# pcb.net
KiCad netlist of a schematic drawn in EasyEDA
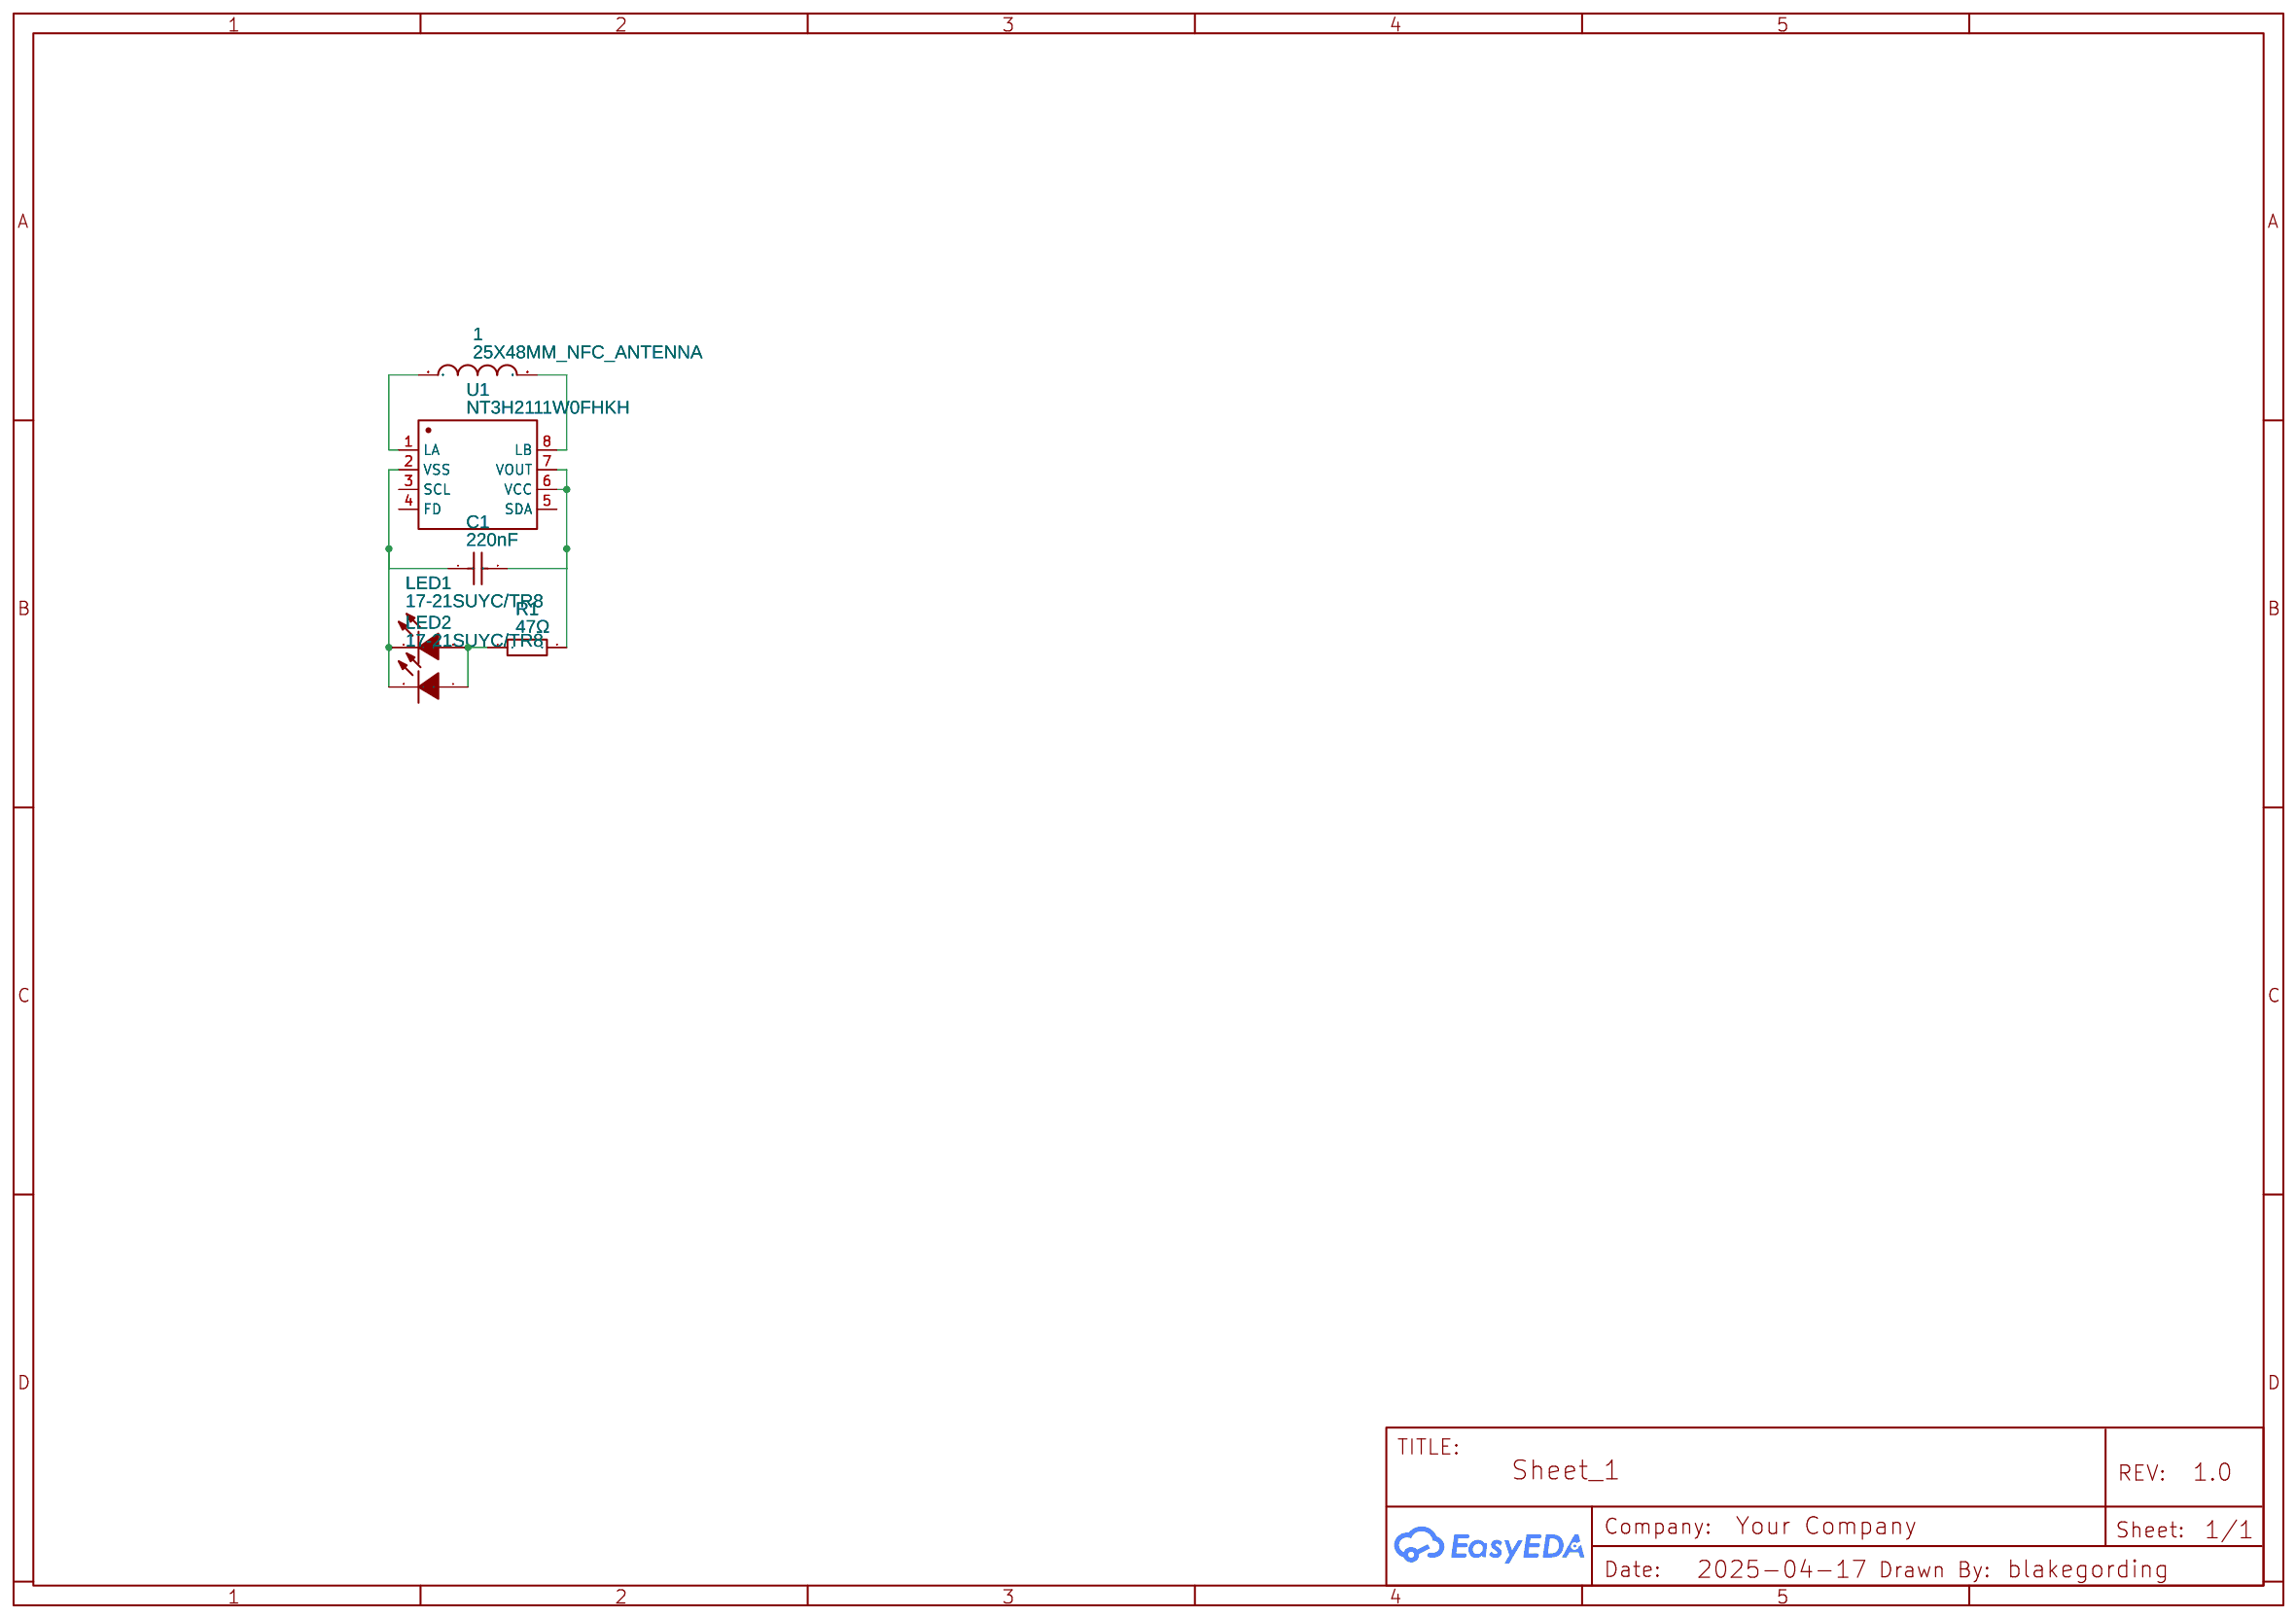
[diagram p0: schematic sheet]

(export (version "E")
  (design (tool "Eeschema 10.0.6"))
  (components
    (comp (ref "1") (value "25X48MM_NFC_ANTENNA") (libsource (lib "") (part "25X48MM_NFC_ANTENNA")))
    (comp (ref "C1")
      (value "220nF")
      (fields
        (field (name "Manufacturer Part") "CL10B224KA8NNNC")
        (field (name "Manufacturer") "SAMSUNG(三星)")
      )
      (libsource (lib "") (part "CL10B224KA8NNNC"))
    )
    (comp (ref "LED1")
      (value "17-21SUYC/TR8")
      (fields (field (name "Manufacturer Part") "KT-0805黄灯") (field (name "Manufacturer") "KENTO"))
      (libsource (lib "") (part "17-21SUYC/TR8"))
    )
    (comp (ref "LED2")
      (value "17-21SUYC/TR8")
      (fields (field (name "Manufacturer Part") "KT-0805黄灯") (field (name "Manufacturer") "KENTO"))
      (libsource (lib "") (part "17-21SUYC/TR8"))
    )
    (comp (ref "R1")
      (value "47Ω")
      (fields
        (field (name "Manufacturer Part") "0603WAF470JT5E")
        (field (name "Manufacturer") "UNI-ROYAL(厚声)")
      )
      (libsource (lib "") (part "0603WAF470JT5E"))
    )
    (comp (ref "U1")
      (value "NT3H2111W0FHKH")
      (fields (field (name "Manufacturer") "NXP(恩智浦)"))
      (libsource (lib "") (part "NT3H2111W0FHKH"))
    )
  )
  (nets
    (net (code "1") (name "Net-(LED1-+)") (class "Default")
      (node (ref "LED1") (pin "1") (pinfunction "+_1") (pintype "unspecified"))
      (node (ref "LED2") (pin "1") (pinfunction "+_1") (pintype "unspecified"))
      (node (ref "R1") (pin "1") (pinfunction "1_1") (pintype "input"))
    )
    (net (code "2") (name "Net-(LED1--)") (class "Default")
      (node (ref "C1") (pin "1") (pinfunction "1_1") (pintype "input"))
      (node (ref "LED1") (pin "2") (pinfunction "-_2") (pintype "unspecified"))
      (node (ref "LED2") (pin "2") (pinfunction "-_2") (pintype "unspecified"))
      (node (ref "U1") (pin "2") (pinfunction "VSS_2") (pintype "unspecified"))
    )
    (net (code "3") (name "Net-(U1-LA)") (class "Default")
      (node (ref "1") (pin "P$1") (pinfunction "P$1_P$1") (pintype "bidirectional"))
      (node (ref "U1") (pin "1") (pinfunction "LA_1") (pintype "unspecified"))
    )
    (net (code "4") (name "Net-(U1-LB)") (class "Default")
      (node (ref "1") (pin "P$2") (pinfunction "P$2_P$2") (pintype "bidirectional"))
      (node (ref "U1") (pin "8") (pinfunction "LB_8") (pintype "unspecified"))
    )
    (net (code "5") (name "Net-(U1-VCC)") (class "Default")
      (node (ref "C1") (pin "2") (pinfunction "2_2") (pintype "input"))
      (node (ref "R1") (pin "2") (pinfunction "2_2") (pintype "input"))
      (node (ref "U1") (pin "6") (pinfunction "VCC_6") (pintype "unspecified"))
      (node (ref "U1") (pin "7") (pinfunction "VOUT_7") (pintype "unspecified"))
    )
    (net (code "6") (name "unconnected-(U1-FD-Pad4)") (class "Default")
      (node (ref "U1") (pin "4") (pinfunction "FD_4") (pintype "unspecified"))
    )
    (net (code "7") (name "unconnected-(U1-SCL-Pad3)") (class "Default")
      (node (ref "U1") (pin "3") (pinfunction "SCL_3") (pintype "unspecified"))
    )
    (net (code "8") (name "unconnected-(U1-SDA-Pad5)") (class "Default")
      (node (ref "U1") (pin "5") (pinfunction "SDA_5") (pintype "unspecified"))
    )
  )
)
